# DEVICE.net
KiCad netlist of a schematic drawn in Altium Designer
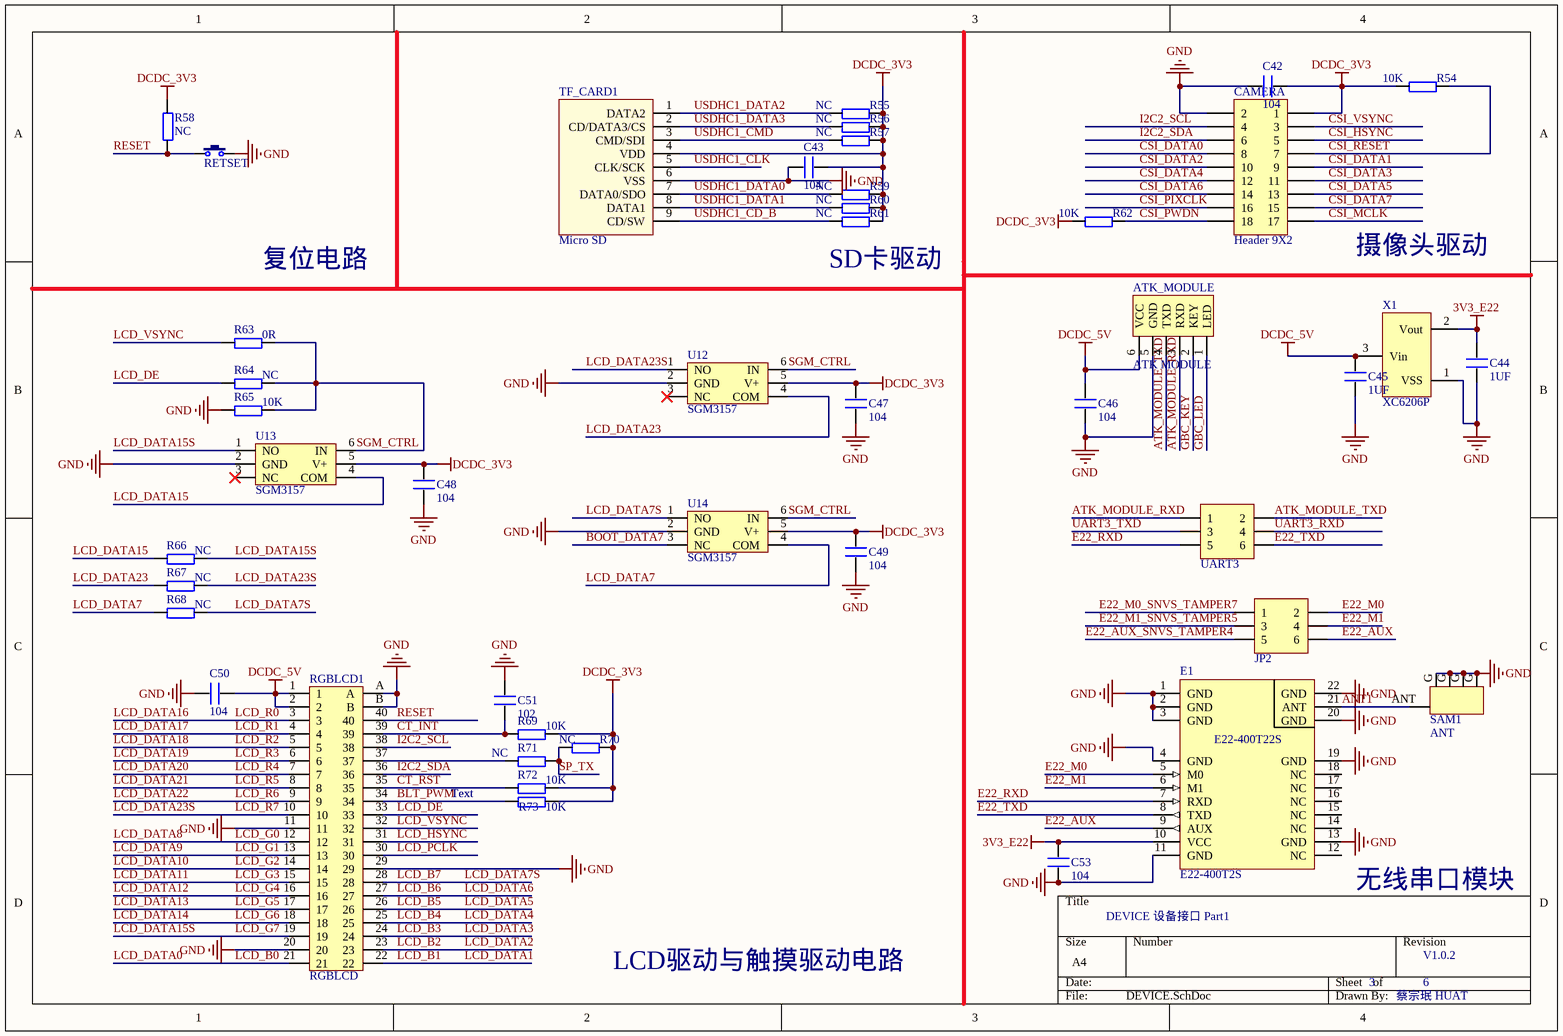
[diagram p0: DEVICE.SchDoc]

(export (version "E")
  (design (tool "Eeschema 10.0.6"))
  (components
    (comp (ref "ATK_MODULE")
      (value "ATK MODULE")
      (footprint "HEAD6")
      (description "ATK-HC05")
      (libsource (lib "IMX6UL_ALPHA(底板)_V2.0") (part "ATK-HC05"))
    )
    (comp (ref "C42") (value "104") (footprint "C_0603P") (libsource (lib "ZZW封装汇总") (part "C")))
    (comp (ref "C43") (value "104") (footprint "C_0603P") (libsource (lib "ZZW封装汇总") (part "C")))
    (comp (ref "C44") (value "1UF") (footprint "C_0603P") (libsource (lib "ZZW封装汇总") (part "C")))
    (comp (ref "C45") (value "1UF") (footprint "C_0603P") (libsource (lib "ZZW封装汇总") (part "C")))
    (comp (ref "C46") (value "104") (footprint "C_0603P") (libsource (lib "ZZW封装汇总") (part "C")))
    (comp (ref "C47") (value "104") (footprint "C_0603P") (libsource (lib "ZZW封装汇总") (part "C")))
    (comp (ref "C48") (value "104") (footprint "C_0603P") (libsource (lib "ZZW封装汇总") (part "C")))
    (comp (ref "C49") (value "104") (footprint "C_0603P") (libsource (lib "ZZW封装汇总") (part "C")))
    (comp (ref "C50") (value "104") (footprint "C_0603P") (libsource (lib "ZZW封装汇总") (part "C")))
    (comp (ref "C51") (value "102") (footprint "C_0603P") (libsource (lib "ZZW封装汇总") (part "C")))
    (comp (ref "C53") (value "104") (footprint "C_0603P") (libsource (lib "ZZW封装汇总") (part "C")))
    (comp (ref "CAMERA")
      (value "Header 9X2")
      (footprint "HDR2X9")
      (description "Header, 9-Pin, Dual row")
      (fields (field (name "PUBLISHER") "Altium Limited"))
      (libsource (lib "IMX6UL_ALPHA(底板)_V2.0") (part "Header 9X2"))
    )
    (comp (ref "E1")
      (value "E22-400T2S")
      (footprint "PE22-400T22S")
      (libsource (lib "ZZW封装汇总") (part "E22-400T2S"))
    )
    (comp (ref "JP2")
      (value "RS232/RS485")
      (footprint "HDR-3X2")
      (description "3*2P接插件")
      (fields (field (name "版权归属") "源创客"))
      (libsource (lib "IMX6UL_ALPHA(底板)_V2.0") (part "Header 3X2"))
    )
    (comp (ref "R54") (value "10K") (footprint "R_0603P") (libsource (lib "ZZW封装汇总") (part "R")))
    (comp (ref "R55") (value "NC") (footprint "R_0603P") (libsource (lib "ZZW封装汇总") (part "R")))
    (comp (ref "R56") (value "NC") (footprint "R_0603P") (libsource (lib "ZZW封装汇总") (part "R")))
    (comp (ref "R57") (value "NC") (footprint "R_0603P") (libsource (lib "ZZW封装汇总") (part "R")))
    (comp (ref "R58") (value "NC") (footprint "R_0603P") (libsource (lib "ZZW封装汇总") (part "R")))
    (comp (ref "R59") (value "NC") (footprint "R_0603P") (libsource (lib "ZZW封装汇总") (part "R")))
    (comp (ref "R60") (value "NC") (footprint "R_0603P") (libsource (lib "ZZW封装汇总") (part "R")))
    (comp (ref "R61") (value "NC") (footprint "R_0603P") (libsource (lib "ZZW封装汇总") (part "R")))
    (comp (ref "R62") (value "10K") (footprint "R_0603P") (libsource (lib "ZZW封装汇总") (part "R")))
    (comp (ref "R63") (value "0R") (footprint "R_0603P") (libsource (lib "ZZW封装汇总") (part "R")))
    (comp (ref "R64") (value "NC") (footprint "R_0603P") (libsource (lib "ZZW封装汇总") (part "R")))
    (comp (ref "R65") (value "10K") (footprint "R_0603P") (libsource (lib "ZZW封装汇总") (part "R")))
    (comp (ref "R66") (value "NC") (footprint "R_0603P") (libsource (lib "ZZW封装汇总") (part "R")))
    (comp (ref "R67") (value "NC") (footprint "R_0603P") (libsource (lib "ZZW封装汇总") (part "R")))
    (comp (ref "R68") (value "NC") (footprint "R_0603P") (libsource (lib "ZZW封装汇总") (part "R")))
    (comp (ref "R69") (value "10K") (footprint "R_0603P") (libsource (lib "ZZW封装汇总") (part "R")))
    (comp (ref "R70") (value "NC") (footprint "R_0603P") (libsource (lib "ZZW封装汇总") (part "R")))
    (comp (ref "R71") (value "NC") (footprint "R_0603P") (libsource (lib "ZZW封装汇总") (part "R")))
    (comp (ref "R72") (value "10K") (footprint "R_0603P") (libsource (lib "ZZW封装汇总") (part "R")))
    (comp (ref "R73") (value "10K") (footprint "R_0603P") (libsource (lib "ZZW封装汇总") (part "R")))
    (comp (ref "RETSET")
      (value "KEY")
      (footprint "TSW DIP-6*6*5 - 2")
      (description "按键")
      (fields (field (name "版权归属") "源创客"))
      (libsource (lib "IMX6UL_ALPHA(底板)_V2.0") (part "KEY"))
    )
    (comp (ref "RGBLCD1")
      (value "RGBLCD")
      (footprint "FPC0.5-TOP40P")
      (description "FPC-40P-0.5mm")
      (libsource (lib "IMX6UL_ALPHA(底板)_V2.0") (part "FPC-40"))
    )
    (comp (ref "SAM1") (value "ANT") (footprint "SMA-KE") (libsource (lib "ZZW封装汇总") (part "SAM-DIP 天线座")))
    (comp (ref "TF_CARD1")
      (value "Micro SD")
      (footprint "Micro SD")
      (description "Micro SD卡")
      (fields (field (name "版权归属") "源创客"))
      (libsource (lib "IMX6UL_ALPHA(底板)_V2.0") (part "Micro SD"))
    )
    (comp (ref "U12")
      (value "SGM3157")
      (footprint "SOT363-6L")
      (description "单路双掷模拟开关")
      (libsource (lib "IMX6UL_ALPHA(底板)_V2.0") (part "SGM3157"))
    )
    (comp (ref "U13")
      (value "SGM3157")
      (footprint "SOT363-6L")
      (description "单路双掷模拟开关")
      (libsource (lib "IMX6UL_ALPHA(底板)_V2.0") (part "SGM3157"))
    )
    (comp (ref "U14")
      (value "SGM3157")
      (footprint "SOT363-6L")
      (description "单路双掷模拟开关")
      (libsource (lib "IMX6UL_ALPHA(底板)_V2.0") (part "SGM3157"))
    )
    (comp (ref "UART3")
      (value "RS232/RS485")
      (footprint "HDR-3X2")
      (description "3*2P接插件")
      (fields (field (name "版权归属") "源创客"))
      (libsource (lib "IMX6UL_ALPHA(底板)_V2.0") (part "Header 3X2"))
    )
    (comp (ref "X1")
      (value "XC6206P")
      (footprint "XC6206P332  SOT-23  LDO电源稳压IC")
      (libsource (lib "ZZW封装汇总") (part "XC6206P-332 稳压LDO芯片"))
    )
  )
  (nets
    (net (code "1") (name "/ANT1") (class "Default")
      (node (ref "E1") (pin "21") (pinfunction "ANT_21") (pintype "passive"))
      (node (ref "SAM1") (pin "ANT") (pinfunction "1_ANT") (pintype "passive"))
    )
    (net (code "2") (name "/ATK_MODULE_RXD") (class "Default")
      (node (ref "ATK_MODULE") (pin "3") (pinfunction "RXD_3") (pintype "passive"))
      (node (ref "UART3") (pin "1") (pinfunction "1_1") (pintype "passive"))
    )
    (net (code "3") (name "/ATK_MODULE_TXD") (class "Default")
      (node (ref "ATK_MODULE") (pin "4") (pinfunction "TXD_4") (pintype "passive"))
      (node (ref "UART3") (pin "2") (pinfunction "2_2") (pintype "passive"))
    )
    (net (code "4") (name "/BLT_PWM") (class "Default")
      (node (ref "R73") (pin "1") (pintype "passive"))
      (node (ref "RGBLCD1") (pin "34") (pinfunction "34_34") (pintype "passive"))
    )
    (net (code "5") (name "/BOOT_DATA7") (class "Default")
      (node (ref "U14") (pin "3") (pinfunction "NC_3") (pintype "passive"))
    )
    (net (code "6") (name "/CSI_DATA0") (class "Default")
      (node (ref "CAMERA") (pin "8") (pinfunction "8_8") (pintype "passive"))
    )
    (net (code "7") (name "/CSI_DATA1") (class "Default")
      (node (ref "CAMERA") (pin "9") (pinfunction "9_9") (pintype "passive"))
    )
    (net (code "8") (name "/CSI_DATA2") (class "Default")
      (node (ref "CAMERA") (pin "10") (pinfunction "10_10") (pintype "passive"))
    )
    (net (code "9") (name "/CSI_DATA3") (class "Default")
      (node (ref "CAMERA") (pin "11") (pinfunction "11_11") (pintype "passive"))
    )
    (net (code "10") (name "/CSI_DATA4") (class "Default")
      (node (ref "CAMERA") (pin "12") (pinfunction "12_12") (pintype "passive"))
    )
    (net (code "11") (name "/CSI_DATA5") (class "Default")
      (node (ref "CAMERA") (pin "13") (pinfunction "13_13") (pintype "passive"))
    )
    (net (code "12") (name "/CSI_DATA6") (class "Default")
      (node (ref "CAMERA") (pin "14") (pinfunction "14_14") (pintype "passive"))
    )
    (net (code "13") (name "/CSI_DATA7") (class "Default")
      (node (ref "CAMERA") (pin "15") (pinfunction "15_15") (pintype "passive"))
    )
    (net (code "14") (name "/CSI_HSYNC") (class "Default")
      (node (ref "CAMERA") (pin "5") (pinfunction "5_5") (pintype "passive"))
    )
    (net (code "15") (name "/CSI_MCLK") (class "Default")
      (node (ref "CAMERA") (pin "17") (pinfunction "17_17") (pintype "passive"))
    )
    (net (code "16") (name "/CSI_PIXCLK") (class "Default")
      (node (ref "CAMERA") (pin "16") (pinfunction "16_16") (pintype "passive"))
    )
    (net (code "17") (name "/CSI_PWDN") (class "Default")
      (node (ref "CAMERA") (pin "18") (pinfunction "18_18") (pintype "passive"))
      (node (ref "R62") (pin "2") (pintype "passive"))
    )
    (net (code "18") (name "/CSI_RESET") (class "Default")
      (node (ref "CAMERA") (pin "7") (pinfunction "7_7") (pintype "passive"))
      (node (ref "R54") (pin "2") (pintype "passive"))
    )
    (net (code "19") (name "/CSI_VSYNC") (class "Default")
      (node (ref "CAMERA") (pin "3") (pinfunction "3_3") (pintype "passive"))
    )
    (net (code "20") (name "/CT_INT") (class "Default")
      (node (ref "C51") (pin "1") (pintype "passive"))
      (node (ref "R69") (pin "1") (pintype "passive"))
      (node (ref "RGBLCD1") (pin "39") (pinfunction "39_39") (pintype "passive"))
    )
    (net (code "21") (name "/CT_RST") (class "Default")
      (node (ref "R72") (pin "1") (pintype "passive"))
      (node (ref "RGBLCD1") (pin "35") (pinfunction "35_35") (pintype "passive"))
    )
    (net (code "22") (name "/E22_AUX") (class "Default")
      (node (ref "E1") (pin "9") (pinfunction "AUX_9") (pintype "output"))
      (node (ref "JP2") (pin "6") (pinfunction "6_6") (pintype "passive"))
    )
    (net (code "23") (name "/E22_AUX_SNVS_TAMPER4") (class "Default")
      (node (ref "JP2") (pin "5") (pinfunction "5_5") (pintype "passive"))
    )
    (net (code "24") (name "/E22_M0") (class "Default")
      (node (ref "E1") (pin "5") (pinfunction "M0_5") (pintype "input"))
      (node (ref "JP2") (pin "2") (pinfunction "2_2") (pintype "passive"))
    )
    (net (code "25") (name "/E22_M0_SNVS_TAMPER7") (class "Default")
      (node (ref "JP2") (pin "1") (pinfunction "1_1") (pintype "passive"))
    )
    (net (code "26") (name "/E22_M1") (class "Default")
      (node (ref "E1") (pin "6") (pinfunction "M1_6") (pintype "input"))
      (node (ref "JP2") (pin "4") (pinfunction "4_4") (pintype "passive"))
    )
    (net (code "27") (name "/E22_M1_SNVS_TAMPER5") (class "Default")
      (node (ref "JP2") (pin "3") (pinfunction "3_3") (pintype "passive"))
    )
    (net (code "28") (name "/E22_RXD") (class "Default")
      (node (ref "E1") (pin "7") (pinfunction "RXD_7") (pintype "input"))
      (node (ref "UART3") (pin "5") (pinfunction "5_5") (pintype "passive"))
    )
    (net (code "29") (name "/E22_TXD") (class "Default")
      (node (ref "E1") (pin "8") (pinfunction "TXD_8") (pintype "output"))
      (node (ref "UART3") (pin "6") (pinfunction "6_6") (pintype "passive"))
    )
    (net (code "30") (name "/GBC_KEY") (class "Default")
      (node (ref "ATK_MODULE") (pin "2") (pinfunction "KEY_2") (pintype "passive"))
    )
    (net (code "31") (name "/GBC_LED") (class "Default")
      (node (ref "ATK_MODULE") (pin "1") (pinfunction "LED_1") (pintype "passive"))
    )
    (net (code "32") (name "/I2C2_SCL") (class "Default")
      (node (ref "CAMERA") (pin "4") (pinfunction "4_4") (pintype "passive"))
      (node (ref "RGBLCD1") (pin "38") (pinfunction "38_38") (pintype "passive"))
    )
    (net (code "33") (name "/I2C2_SDA") (class "Default")
      (node (ref "CAMERA") (pin "6") (pinfunction "6_6") (pintype "passive"))
      (node (ref "RGBLCD1") (pin "36") (pinfunction "36_36") (pintype "passive"))
    )
    (net (code "34") (name "/LCD_B0") (class "Default")
      (node (ref "RGBLCD1") (pin "21") (pinfunction "21_21") (pintype "passive"))
    )
    (net (code "35") (name "/LCD_B1") (class "Default")
      (node (ref "RGBLCD1") (pin "22") (pinfunction "22_22") (pintype "passive"))
    )
    (net (code "36") (name "/LCD_B2") (class "Default")
      (node (ref "RGBLCD1") (pin "23") (pinfunction "23_23") (pintype "passive"))
    )
    (net (code "37") (name "/LCD_B3") (class "Default")
      (node (ref "RGBLCD1") (pin "24") (pinfunction "24_24") (pintype "passive"))
    )
    (net (code "38") (name "/LCD_B4") (class "Default")
      (node (ref "RGBLCD1") (pin "25") (pinfunction "25_25") (pintype "passive"))
    )
    (net (code "39") (name "/LCD_B5") (class "Default")
      (node (ref "RGBLCD1") (pin "26") (pinfunction "26_26") (pintype "passive"))
    )
    (net (code "40") (name "/LCD_B6") (class "Default")
      (node (ref "RGBLCD1") (pin "27") (pinfunction "27_27") (pintype "passive"))
    )
    (net (code "41") (name "/LCD_B7") (class "Default")
      (node (ref "R68") (pin "2") (pintype "passive"))
      (node (ref "RGBLCD1") (pin "28") (pinfunction "28_28") (pintype "passive"))
      (node (ref "U14") (pin "1") (pinfunction "NO_1") (pintype "passive"))
    )
    (net (code "42") (name "/LCD_DATA7") (class "Default")
      (node (ref "R68") (pin "1") (pintype "passive"))
      (node (ref "U14") (pin "4") (pinfunction "COM_4") (pintype "passive"))
    )
    (net (code "43") (name "/LCD_DATA8") (class "Default")
      (node (ref "RGBLCD1") (pin "12") (pinfunction "12_12") (pintype "passive"))
    )
    (net (code "44") (name "/LCD_DATA9") (class "Default")
      (node (ref "RGBLCD1") (pin "13") (pinfunction "13_13") (pintype "passive"))
    )
    (net (code "45") (name "/LCD_DATA10") (class "Default")
      (node (ref "RGBLCD1") (pin "14") (pinfunction "14_14") (pintype "passive"))
    )
    (net (code "46") (name "/LCD_DATA11") (class "Default")
      (node (ref "RGBLCD1") (pin "15") (pinfunction "15_15") (pintype "passive"))
    )
    (net (code "47") (name "/LCD_DATA12") (class "Default")
      (node (ref "RGBLCD1") (pin "16") (pinfunction "16_16") (pintype "passive"))
    )
    (net (code "48") (name "/LCD_DATA13") (class "Default")
      (node (ref "RGBLCD1") (pin "17") (pinfunction "17_17") (pintype "passive"))
    )
    (net (code "49") (name "/LCD_DATA14") (class "Default")
      (node (ref "RGBLCD1") (pin "18") (pinfunction "18_18") (pintype "passive"))
    )
    (net (code "50") (name "/LCD_DATA15") (class "Default")
      (node (ref "R66") (pin "1") (pintype "passive"))
      (node (ref "U13") (pin "4") (pinfunction "COM_4") (pintype "passive"))
    )
    (net (code "51") (name "/LCD_DATA15S") (class "Default")
      (node (ref "R66") (pin "2") (pintype "passive"))
      (node (ref "RGBLCD1") (pin "19") (pinfunction "19_19") (pintype "passive"))
      (node (ref "U13") (pin "1") (pinfunction "NO_1") (pintype "passive"))
    )
    (net (code "52") (name "/LCD_DATA16") (class "Default")
      (node (ref "RGBLCD1") (pin "3") (pinfunction "3_3") (pintype "passive"))
    )
    (net (code "53") (name "/LCD_DATA17") (class "Default")
      (node (ref "RGBLCD1") (pin "4") (pinfunction "4_4") (pintype "passive"))
    )
    (net (code "54") (name "/LCD_DATA18") (class "Default")
      (node (ref "RGBLCD1") (pin "5") (pinfunction "5_5") (pintype "passive"))
    )
    (net (code "55") (name "/LCD_DATA19") (class "Default")
      (node (ref "RGBLCD1") (pin "6") (pinfunction "6_6") (pintype "passive"))
    )
    (net (code "56") (name "/LCD_DATA20") (class "Default")
      (node (ref "RGBLCD1") (pin "7") (pinfunction "7_7") (pintype "passive"))
    )
    (net (code "57") (name "/LCD_DATA21") (class "Default")
      (node (ref "RGBLCD1") (pin "8") (pinfunction "8_8") (pintype "passive"))
    )
    (net (code "58") (name "/LCD_DATA22") (class "Default")
      (node (ref "RGBLCD1") (pin "9") (pinfunction "9_9") (pintype "passive"))
    )
    (net (code "59") (name "/LCD_DATA23") (class "Default")
      (node (ref "R67") (pin "1") (pintype "passive"))
      (node (ref "U12") (pin "4") (pinfunction "COM_4") (pintype "passive"))
    )
    (net (code "60") (name "/LCD_DATA23S") (class "Default")
      (node (ref "R67") (pin "2") (pintype "passive"))
      (node (ref "RGBLCD1") (pin "10") (pinfunction "10_10") (pintype "passive"))
      (node (ref "U12") (pin "1") (pinfunction "NO_1") (pintype "passive"))
    )
    (net (code "61") (name "/LCD_DE") (class "Default")
      (node (ref "R64") (pin "1") (pintype "passive"))
      (node (ref "RGBLCD1") (pin "33") (pinfunction "33_33") (pintype "passive"))
    )
    (net (code "62") (name "/LCD_HSYNC") (class "Default")
      (node (ref "RGBLCD1") (pin "31") (pinfunction "31_31") (pintype "passive"))
    )
    (net (code "63") (name "/LCD_PCLK") (class "Default")
      (node (ref "RGBLCD1") (pin "30") (pinfunction "30_30") (pintype "passive"))
    )
    (net (code "64") (name "/LCD_VSYNC") (class "Default")
      (node (ref "R63") (pin "1") (pintype "passive"))
      (node (ref "RGBLCD1") (pin "32") (pinfunction "32_32") (pintype "passive"))
    )
    (net (code "65") (name "/RESET") (class "Default")
      (node (ref "R58") (pin "1") (pintype "passive"))
      (node (ref "RETSET") (pin "1") (pinfunction "1_1") (pintype "passive"))
      (node (ref "RGBLCD1") (pin "40") (pinfunction "40_40") (pintype "passive"))
    )
    (net (code "66") (name "/SGM_CTRL") (class "Default")
      (node (ref "R63") (pin "2") (pintype "passive"))
      (node (ref "R64") (pin "2") (pintype "passive"))
      (node (ref "R65") (pin "2") (pintype "passive"))
      (node (ref "U12") (pin "6") (pinfunction "IN_6") (pintype "passive"))
      (node (ref "U13") (pin "6") (pinfunction "IN_6") (pintype "passive"))
      (node (ref "U14") (pin "6") (pinfunction "IN_6") (pintype "passive"))
    )
    (net (code "67") (name "/SP_TX") (class "Default")
      (node (ref "R70") (pin "1") (pintype "passive"))
      (node (ref "R71") (pin "2") (pintype "passive"))
    )
    (net (code "68") (name "/UART3_RXD") (class "Default")
      (node (ref "UART3") (pin "4") (pinfunction "4_4") (pintype "passive"))
    )
    (net (code "69") (name "/UART3_TXD") (class "Default")
      (node (ref "UART3") (pin "3") (pinfunction "3_3") (pintype "passive"))
    )
    (net (code "70") (name "/USDHC1_CD_B") (class "Default")
      (node (ref "R61") (pin "1") (pintype "passive"))
      (node (ref "TF_CARD1") (pin "9") (pinfunction "CD/SW_9") (pintype "passive"))
    )
    (net (code "71") (name "/USDHC1_CLK") (class "Default")
      (node (ref "TF_CARD1") (pin "5") (pinfunction "CLK/SCK_5") (pintype "passive"))
    )
    (net (code "72") (name "/USDHC1_CMD") (class "Default")
      (node (ref "R57") (pin "1") (pintype "passive"))
      (node (ref "TF_CARD1") (pin "3") (pinfunction "CMD/SDI_3") (pintype "passive"))
    )
    (net (code "73") (name "/USDHC1_DATA0") (class "Default")
      (node (ref "R59") (pin "1") (pintype "passive"))
      (node (ref "TF_CARD1") (pin "7") (pinfunction "DATA0/SDO_7") (pintype "passive"))
    )
    (net (code "74") (name "/USDHC1_DATA1") (class "Default")
      (node (ref "R60") (pin "1") (pintype "passive"))
      (node (ref "TF_CARD1") (pin "8") (pinfunction "DATA1_8") (pintype "passive"))
    )
    (net (code "75") (name "/USDHC1_DATA2") (class "Default")
      (node (ref "R55") (pin "1") (pintype "passive"))
      (node (ref "TF_CARD1") (pin "1") (pinfunction "DATA2_1") (pintype "passive"))
    )
    (net (code "76") (name "/USDHC1_DATA3") (class "Default")
      (node (ref "R56") (pin "1") (pintype "passive"))
      (node (ref "TF_CARD1") (pin "2") (pinfunction "CD/DATA3/CS_2") (pintype "passive"))
    )
    (net (code "77") (name "3V3_E22") (class "Default")
      (node (ref "C44") (pin "2") (pintype "passive"))
      (node (ref "C53") (pin "2") (pintype "passive"))
      (node (ref "E1") (pin "10") (pinfunction "VCC_10") (pintype "passive"))
      (node (ref "X1") (pin "2") (pinfunction "Vout_2") (pintype "passive"))
    )
    (net (code "78") (name "DCDC_3V3") (class "Default")
      (node (ref "C42") (pin "2") (pintype "passive"))
      (node (ref "C43") (pin "2") (pintype "passive"))
      (node (ref "C47") (pin "2") (pintype "passive"))
      (node (ref "C48") (pin "2") (pintype "passive"))
      (node (ref "C49") (pin "2") (pintype "passive"))
      (node (ref "CAMERA") (pin "1") (pinfunction "1_1") (pintype "passive"))
      (node (ref "R54") (pin "1") (pintype "passive"))
      (node (ref "R55") (pin "2") (pintype "passive"))
      (node (ref "R56") (pin "2") (pintype "passive"))
      (node (ref "R57") (pin "2") (pintype "passive"))
      (node (ref "R58") (pin "2") (pintype "passive"))
      (node (ref "R59") (pin "2") (pintype "passive"))
      (node (ref "R60") (pin "2") (pintype "passive"))
      (node (ref "R61") (pin "2") (pintype "passive"))
      (node (ref "R62") (pin "1") (pintype "passive"))
      (node (ref "R69") (pin "2") (pintype "passive"))
      (node (ref "R70") (pin "2") (pintype "passive"))
      (node (ref "R72") (pin "2") (pintype "passive"))
      (node (ref "R73") (pin "2") (pintype "passive"))
      (node (ref "TF_CARD1") (pin "4") (pinfunction "VDD_4") (pintype "passive"))
      (node (ref "U12") (pin "5") (pinfunction "V+_5") (pintype "passive"))
      (node (ref "U13") (pin "5") (pinfunction "V+_5") (pintype "passive"))
      (node (ref "U14") (pin "5") (pinfunction "V+_5") (pintype "passive"))
    )
    (net (code "79") (name "DCDC_5V") (class "Default")
      (node (ref "ATK_MODULE") (pin "6") (pinfunction "VCC_6") (pintype "passive"))
      (node (ref "C45") (pin "2") (pintype "passive"))
      (node (ref "C46") (pin "2") (pintype "passive"))
      (node (ref "C50") (pin "2") (pintype "passive"))
      (node (ref "RGBLCD1") (pin "1") (pinfunction "1_1") (pintype "passive"))
      (node (ref "RGBLCD1") (pin "2") (pinfunction "2_2") (pintype "passive"))
      (node (ref "X1") (pin "3") (pinfunction "Vin_3") (pintype "passive"))
    )
    (net (code "80") (name "GND") (class "Default")
      (node (ref "ATK_MODULE") (pin "5") (pinfunction "GND_5") (pintype "passive"))
      (node (ref "C42") (pin "1") (pintype "passive"))
      (node (ref "C43") (pin "1") (pintype "passive"))
      (node (ref "C44") (pin "1") (pintype "passive"))
      (node (ref "C45") (pin "1") (pintype "passive"))
      (node (ref "C46") (pin "1") (pintype "passive"))
      (node (ref "C47") (pin "1") (pintype "passive"))
      (node (ref "C48") (pin "1") (pintype "passive"))
      (node (ref "C49") (pin "1") (pintype "passive"))
      (node (ref "C50") (pin "1") (pintype "passive"))
      (node (ref "C51") (pin "2") (pintype "passive"))
      (node (ref "C53") (pin "1") (pintype "passive"))
      (node (ref "CAMERA") (pin "2") (pinfunction "2_2") (pintype "passive"))
      (node (ref "E1") (pin "1") (pinfunction "GND_1") (pintype "passive"))
      (node (ref "E1") (pin "11") (pinfunction "GND_11") (pintype "passive"))
      (node (ref "E1") (pin "13") (pinfunction "GND_13") (pintype "passive"))
      (node (ref "E1") (pin "19") (pinfunction "GND_19") (pintype "passive"))
      (node (ref "E1") (pin "2") (pinfunction "GND_2") (pintype "passive"))
      (node (ref "E1") (pin "20") (pinfunction "GND_20") (pintype "passive"))
      (node (ref "E1") (pin "22") (pinfunction "GND_22") (pintype "passive"))
      (node (ref "E1") (pin "3") (pinfunction "GND_3") (pintype "passive"))
      (node (ref "E1") (pin "4") (pinfunction "GND_4") (pintype "passive"))
      (node (ref "R65") (pin "1") (pintype "passive"))
      (node (ref "RETSET") (pin "2") (pinfunction "2_2") (pintype "passive"))
      (node (ref "RGBLCD1") (pin "11") (pinfunction "11_11") (pintype "passive"))
      (node (ref "RGBLCD1") (pin "20") (pinfunction "20_20") (pintype "passive"))
      (node (ref "RGBLCD1") (pin "29") (pinfunction "29_29") (pintype "passive"))
      (node (ref "RGBLCD1") (pin "A") (pinfunction "A_A") (pintype "passive"))
      (node (ref "RGBLCD1") (pin "B") (pinfunction "B_B") (pintype "passive"))
      (node (ref "SAM1") (pin "G") (pintype "passive"))
      (node (ref "TF_CARD1") (pin "6") (pinfunction "VSS_6") (pintype "passive"))
      (node (ref "U12") (pin "2") (pinfunction "GND_2") (pintype "passive"))
      (node (ref "U13") (pin "2") (pinfunction "GND_2") (pintype "passive"))
      (node (ref "U14") (pin "2") (pinfunction "GND_2") (pintype "passive"))
      (node (ref "X1") (pin "1") (pinfunction "VSS_1") (pintype "passive"))
    )
    (net (code "81") (name "Net-(R71-Pad1)") (class "Default")
      (node (ref "R71") (pin "1") (pintype "passive"))
      (node (ref "RGBLCD1") (pin "37") (pinfunction "37_37") (pintype "passive"))
    )
    (net (code "82") (name "unconnected-(E1-NC-Pad12)") (class "Default")
      (node (ref "E1") (pin "12") (pinfunction "NC_12") (pintype "passive"))
    )
    (net (code "83") (name "unconnected-(E1-NC-Pad14)") (class "Default")
      (node (ref "E1") (pin "14") (pinfunction "NC_14") (pintype "passive"))
    )
    (net (code "84") (name "unconnected-(E1-NC-Pad15)") (class "Default")
      (node (ref "E1") (pin "15") (pinfunction "NC_15") (pintype "passive"))
    )
    (net (code "85") (name "unconnected-(E1-NC-Pad16)") (class "Default")
      (node (ref "E1") (pin "16") (pinfunction "NC_16") (pintype "passive"))
    )
    (net (code "86") (name "unconnected-(E1-NC-Pad17)") (class "Default")
      (node (ref "E1") (pin "17") (pinfunction "NC_17") (pintype "passive"))
    )
    (net (code "87") (name "unconnected-(E1-NC-Pad18)") (class "Default")
      (node (ref "E1") (pin "18") (pinfunction "NC_18") (pintype "passive"))
    )
    (net (code "88") (name "unconnected-(U12-NC-Pad3)") (class "Default")
      (node (ref "U12") (pin "3") (pinfunction "NC_3") (pintype "passive+no_connect"))
    )
    (net (code "89") (name "unconnected-(U13-NC-Pad3)") (class "Default")
      (node (ref "U13") (pin "3") (pinfunction "NC_3") (pintype "passive+no_connect"))
    )
  )
)
